# MANEA_TCAD_PROIECT_Sheet1.net
KiCad netlist of a schematic drawn in Altium Designer
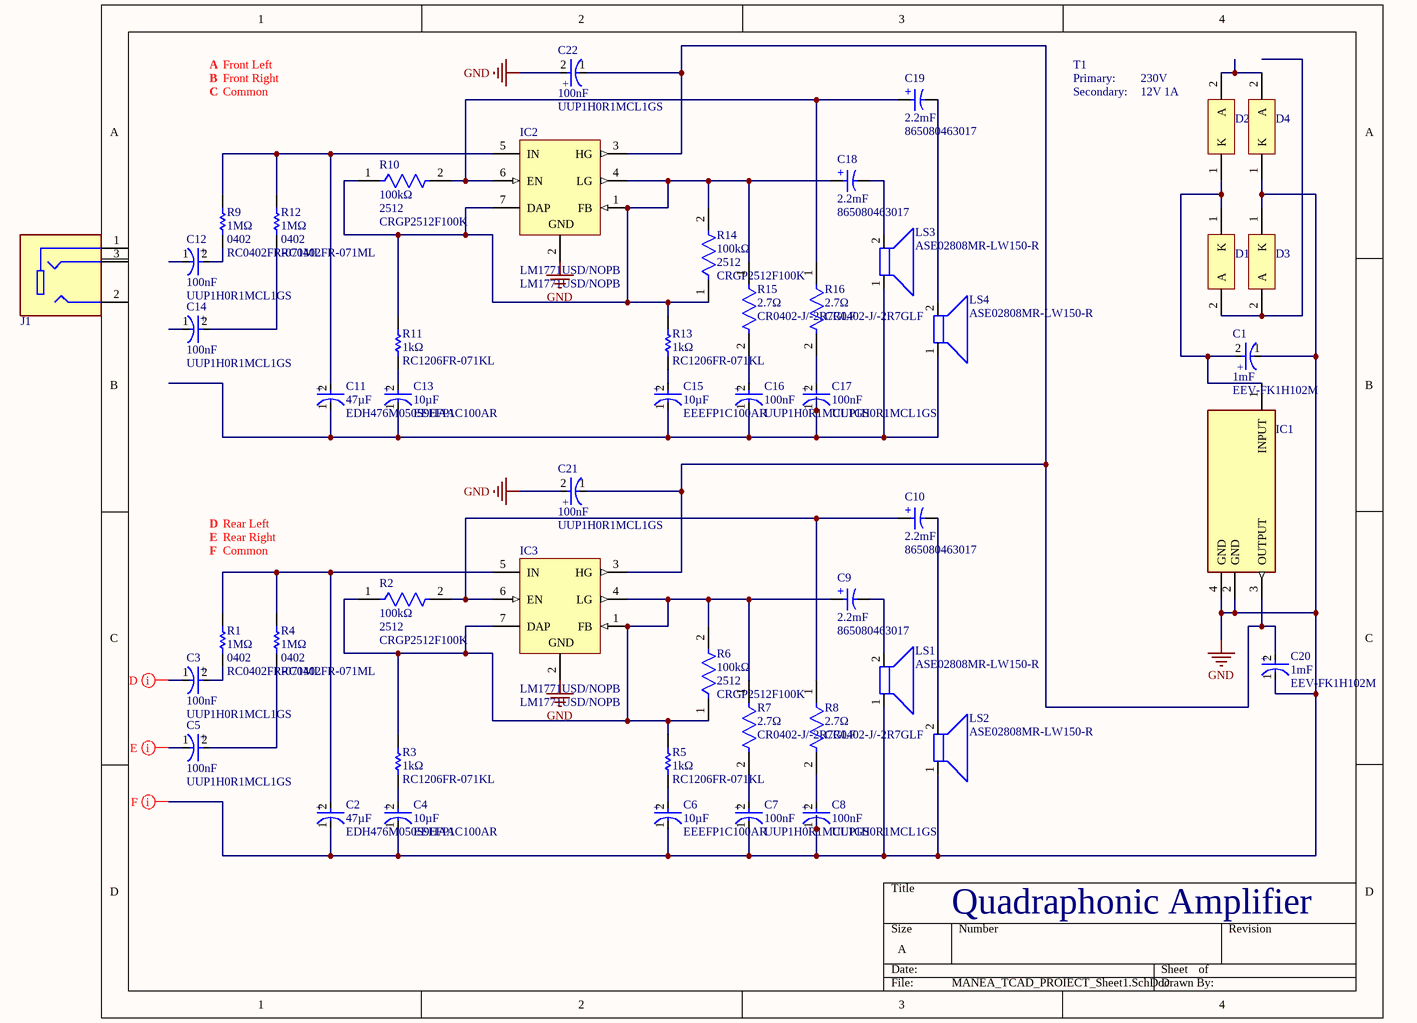
[diagram p0: MANEA_TCAD_PROIECT_Sheet1.SchDoc]

(export (version "E")
  (design (tool "Eeschema 10.0.6"))
  (components
    (comp (ref "C1")
      (value "EEV-FK1H102M")
      (footprint "FP-FK-J16-MFG")
      (description "Radial Can - SMD ALUMINUM ELECTROLYTIC CAPACITOR FK 50V 1000muF 卤20% 0.630Dia 16.00mm")
      (fields
        (field (name "MANUFACTURER") "Panasonic")
        (field (name "TOLERANCE") "20%")
        (field (name "ALTIUM_VALUE") "1mF")
      )
      (libsource (lib "MANEA_TCAD_PROIECT_Schlib") (part "EEV-FK1H102M"))
    )
    (comp (ref "C2")
      (value "EDH476M050S9HAA")
      (footprint "FP-EDH476M050S9HAA-IPC_A")
      (description "Radial Can - SMD ALUMINUM ELECTROLYTIC CAPACITOR EDH 50V 47muF ±20% 0.248Dia 6.30mm")
      (fields
        (field (name "MANUFACTURER") "Yageo Group")
        (field (name "TOLERANCE") "20%")
        (field (name "ALTIUM_VALUE") "47µF")
      )
      (libsource (lib "MANEA_TCAD_PROIECT_Schlib") (part "EDH476M050S9HAA"))
    )
    (comp (ref "C3")
      (value "UUP1H0R1MCL1GS")
      (footprint "FP-UUP1H0R1MCL1GS-MFG")
      (description "Radial Can - SMD ALUMINUM ELECTROLYTIC CAPACITOR UUP 50V 0.1muF ±20% 0.157Dia 4.00mm")
      (fields
        (field (name "MANUFACTURER") "Nichicon")
        (field (name "TOLERANCE") "20%")
        (field (name "ALTIUM_VALUE") "100nF")
      )
      (libsource (lib "MANEA_TCAD_PROIECT_Schlib") (part "UUP1H0R1MCL1GS"))
    )
    (comp (ref "C4")
      (value "EEEFP1C100AR")
      (footprint "FP-FPB-MFG")
      (description "Capacitor Aluminum 10uF 16VDC 20% 4 X 5.8mm SMD 0.85 Ohm 160mA 2000 hr Embossed T/R")
      (fields
        (field (name "MANUFACTURER") "Panasonic")
        (field (name "TOLERANCE") "20%")
        (field (name "ALTIUM_VALUE") "10µF")
      )
      (libsource (lib "MANEA_TCAD_PROIECT_Schlib") (part "EEEFP1C100AR"))
    )
    (comp (ref "C5")
      (value "UUP1H0R1MCL1GS")
      (footprint "FP-UUP1H0R1MCL1GS-MFG")
      (description "Radial Can - SMD ALUMINUM ELECTROLYTIC CAPACITOR UUP 50V 0.1muF ±20% 0.157Dia 4.00mm")
      (fields
        (field (name "MANUFACTURER") "Nichicon")
        (field (name "TOLERANCE") "20%")
        (field (name "ALTIUM_VALUE") "100nF")
      )
      (libsource (lib "MANEA_TCAD_PROIECT_Schlib") (part "UUP1H0R1MCL1GS"))
    )
    (comp (ref "C6")
      (value "EEEFP1C100AR")
      (footprint "FP-FPB-MFG")
      (description "Capacitor Aluminum 10uF 16VDC 20% 4 X 5.8mm SMD 0.85 Ohm 160mA 2000 hr Embossed T/R")
      (fields
        (field (name "MANUFACTURER") "Panasonic")
        (field (name "TOLERANCE") "20%")
        (field (name "ALTIUM_VALUE") "10µF")
      )
      (libsource (lib "MANEA_TCAD_PROIECT_Schlib") (part "EEEFP1C100AR"))
    )
    (comp (ref "C7")
      (value "UUP1H0R1MCL1GS")
      (footprint "FP-UUP1H0R1MCL1GS-MFG")
      (description "Radial Can - SMD ALUMINUM ELECTROLYTIC CAPACITOR UUP 50V 0.1muF ±20% 0.157Dia 4.00mm")
      (fields
        (field (name "MANUFACTURER") "Nichicon")
        (field (name "TOLERANCE") "20%")
        (field (name "ALTIUM_VALUE") "100nF")
      )
      (libsource (lib "MANEA_TCAD_PROIECT_Schlib") (part "UUP1H0R1MCL1GS"))
    )
    (comp (ref "C8")
      (value "UUP1H0R1MCL1GS")
      (footprint "FP-UUP1H0R1MCL1GS-MFG")
      (description "Radial Can - SMD ALUMINUM ELECTROLYTIC CAPACITOR UUP 50V 0.1muF ±20% 0.157Dia 4.00mm")
      (fields
        (field (name "MANUFACTURER") "Nichicon")
        (field (name "TOLERANCE") "20%")
        (field (name "ALTIUM_VALUE") "100nF")
      )
      (libsource (lib "MANEA_TCAD_PROIECT_Schlib") (part "UUP1H0R1MCL1GS"))
    )
    (comp (ref "C9")
      (value "865080463017")
      (footprint "WCAP-ASLI_D16H17")
      (description "SMD Aluminium Electrolytic Capacitor, WCAP-ASLI Series, 2200 F, 25 V, Radial Can - SMD, 16 mm")
      (fields
        (field (name "MANUFACTURER") "Wurth Elektronik")
        (field (name "TOLERANCE") "20%")
        (field (name "ALTIUM_VALUE") "2.2mF")
      )
      (libsource (lib "MANEA_TCAD_PROIECT_Schlib") (part "865080463017"))
    )
    (comp (ref "C10")
      (value "865080463017")
      (footprint "WCAP-ASLI_D16H17")
      (description "SMD Aluminium Electrolytic Capacitor, WCAP-ASLI Series, 2200 F, 25 V, Radial Can - SMD, 16 mm")
      (fields
        (field (name "MANUFACTURER") "Wurth Elektronik")
        (field (name "TOLERANCE") "20%")
        (field (name "ALTIUM_VALUE") "2.2mF")
      )
      (libsource (lib "MANEA_TCAD_PROIECT_Schlib") (part "865080463017"))
    )
    (comp (ref "C11")
      (value "EDH476M050S9HAA")
      (footprint "FP-EDH476M050S9HAA-IPC_A")
      (description "Radial Can - SMD ALUMINUM ELECTROLYTIC CAPACITOR EDH 50V 47muF ±20% 0.248Dia 6.30mm")
      (fields
        (field (name "MANUFACTURER") "Yageo Group")
        (field (name "TOLERANCE") "20%")
        (field (name "ALTIUM_VALUE") "47µF")
      )
      (libsource (lib "MANEA_TCAD_PROIECT_Schlib") (part "EDH476M050S9HAA"))
    )
    (comp (ref "C12")
      (value "UUP1H0R1MCL1GS")
      (footprint "FP-UUP1H0R1MCL1GS-MFG")
      (description "Radial Can - SMD ALUMINUM ELECTROLYTIC CAPACITOR UUP 50V 0.1muF ±20% 0.157Dia 4.00mm")
      (fields
        (field (name "MANUFACTURER") "Nichicon")
        (field (name "TOLERANCE") "20%")
        (field (name "ALTIUM_VALUE") "100nF")
      )
      (libsource (lib "MANEA_TCAD_PROIECT_Schlib") (part "UUP1H0R1MCL1GS"))
    )
    (comp (ref "C13")
      (value "EEEFP1C100AR")
      (footprint "FP-FPB-MFG")
      (description "Capacitor Aluminum 10uF 16VDC 20% 4 X 5.8mm SMD 0.85 Ohm 160mA 2000 hr Embossed T/R")
      (fields
        (field (name "MANUFACTURER") "Panasonic")
        (field (name "TOLERANCE") "20%")
        (field (name "ALTIUM_VALUE") "10µF")
      )
      (libsource (lib "MANEA_TCAD_PROIECT_Schlib") (part "EEEFP1C100AR"))
    )
    (comp (ref "C14")
      (value "UUP1H0R1MCL1GS")
      (footprint "FP-UUP1H0R1MCL1GS-MFG")
      (description "Radial Can - SMD ALUMINUM ELECTROLYTIC CAPACITOR UUP 50V 0.1muF ±20% 0.157Dia 4.00mm")
      (fields
        (field (name "MANUFACTURER") "Nichicon")
        (field (name "TOLERANCE") "20%")
        (field (name "ALTIUM_VALUE") "100nF")
      )
      (libsource (lib "MANEA_TCAD_PROIECT_Schlib") (part "UUP1H0R1MCL1GS"))
    )
    (comp (ref "C15")
      (value "EEEFP1C100AR")
      (footprint "FP-FPB-MFG")
      (description "Capacitor Aluminum 10uF 16VDC 20% 4 X 5.8mm SMD 0.85 Ohm 160mA 2000 hr Embossed T/R")
      (fields
        (field (name "MANUFACTURER") "Panasonic")
        (field (name "TOLERANCE") "20%")
        (field (name "ALTIUM_VALUE") "10µF")
      )
      (libsource (lib "MANEA_TCAD_PROIECT_Schlib") (part "EEEFP1C100AR"))
    )
    (comp (ref "C16")
      (value "UUP1H0R1MCL1GS")
      (footprint "FP-UUP1H0R1MCL1GS-MFG")
      (description "Radial Can - SMD ALUMINUM ELECTROLYTIC CAPACITOR UUP 50V 0.1muF ±20% 0.157Dia 4.00mm")
      (fields
        (field (name "MANUFACTURER") "Nichicon")
        (field (name "TOLERANCE") "20%")
        (field (name "ALTIUM_VALUE") "100nF")
      )
      (libsource (lib "MANEA_TCAD_PROIECT_Schlib") (part "UUP1H0R1MCL1GS"))
    )
    (comp (ref "C17")
      (value "UUP1H0R1MCL1GS")
      (footprint "FP-UUP1H0R1MCL1GS-MFG")
      (description "Radial Can - SMD ALUMINUM ELECTROLYTIC CAPACITOR UUP 50V 0.1muF ±20% 0.157Dia 4.00mm")
      (fields
        (field (name "MANUFACTURER") "Nichicon")
        (field (name "TOLERANCE") "20%")
        (field (name "ALTIUM_VALUE") "100nF")
      )
      (libsource (lib "MANEA_TCAD_PROIECT_Schlib") (part "UUP1H0R1MCL1GS"))
    )
    (comp (ref "C18")
      (value "865080463017")
      (footprint "WCAP-ASLI_D16H17")
      (description "SMD Aluminium Electrolytic Capacitor, WCAP-ASLI Series, 2200 F, 25 V, Radial Can - SMD, 16 mm")
      (fields
        (field (name "MANUFACTURER") "Wurth Elektronik")
        (field (name "TOLERANCE") "20%")
        (field (name "ALTIUM_VALUE") "2.2mF")
      )
      (libsource (lib "MANEA_TCAD_PROIECT_Schlib") (part "865080463017"))
    )
    (comp (ref "C19")
      (value "865080463017")
      (footprint "WCAP-ASLI_D16H17")
      (description "SMD Aluminium Electrolytic Capacitor, WCAP-ASLI Series, 2200 F, 25 V, Radial Can - SMD, 16 mm")
      (fields
        (field (name "MANUFACTURER") "Wurth Elektronik")
        (field (name "TOLERANCE") "20%")
        (field (name "ALTIUM_VALUE") "2.2mF")
      )
      (libsource (lib "MANEA_TCAD_PROIECT_Schlib") (part "865080463017"))
    )
    (comp (ref "C20")
      (value "EEV-FK1H102M")
      (footprint "FP-FK-J16-MFG")
      (description "Radial Can - SMD ALUMINUM ELECTROLYTIC CAPACITOR FK 50V 1000muF 卤20% 0.630Dia 16.00mm")
      (fields
        (field (name "MANUFACTURER") "Panasonic")
        (field (name "TOLERANCE") "20%")
        (field (name "ALTIUM_VALUE") "1mF")
      )
      (libsource (lib "MANEA_TCAD_PROIECT_Schlib") (part "EEV-FK1H102M"))
    )
    (comp (ref "C21")
      (value "UUP1H0R1MCL1GS")
      (footprint "FP-UUP1H0R1MCL1GS-MFG")
      (description "Radial Can - SMD ALUMINUM ELECTROLYTIC CAPACITOR UUP 50V 0.1muF ±20% 0.157Dia 4.00mm")
      (fields
        (field (name "MANUFACTURER") "Nichicon")
        (field (name "TOLERANCE") "20%")
        (field (name "ALTIUM_VALUE") "100nF")
      )
      (libsource (lib "MANEA_TCAD_PROIECT_Schlib") (part "UUP1H0R1MCL1GS"))
    )
    (comp (ref "C22")
      (value "UUP1H0R1MCL1GS")
      (footprint "FP-UUP1H0R1MCL1GS-MFG")
      (description "Radial Can - SMD ALUMINUM ELECTROLYTIC CAPACITOR UUP 50V 0.1muF ±20% 0.157Dia 4.00mm")
      (fields
        (field (name "MANUFACTURER") "Nichicon")
        (field (name "TOLERANCE") "20%")
        (field (name "ALTIUM_VALUE") "100nF")
      )
      (libsource (lib "MANEA_TCAD_PROIECT_Schlib") (part "UUP1H0R1MCL1GS"))
    )
    (comp (ref "D1")
      (value "1N4001")
      (footprint "ONSC-AXIAL_LEAD-2-59-10_P")
      (description "Rectifier Diode Switching 50V 1A 2-Pin DO-41 Box / DIODE GEN PURP 50V 1A DO41")
      (libsource (lib "MANEA_TCAD_PROIECT_Schlib") (part "D1N4001"))
    )
    (comp (ref "D2")
      (value "1N4001")
      (footprint "ONSC-AXIAL_LEAD-2-59-10_P")
      (description "Rectifier Diode Switching 50V 1A 2-Pin DO-41 Box / DIODE GEN PURP 50V 1A DO41")
      (libsource (lib "") (part "D1N4001_1"))
    )
    (comp (ref "D3")
      (value "1N4001")
      (footprint "ONSC-AXIAL_LEAD-2-59-10_P")
      (description "Rectifier Diode Switching 50V 1A 2-Pin DO-41 Box / DIODE GEN PURP 50V 1A DO41")
      (libsource (lib "MANEA_TCAD_PROIECT_Schlib") (part "D1N4001"))
    )
    (comp (ref "D4")
      (value "1N4001")
      (footprint "ONSC-AXIAL_LEAD-2-59-10_P")
      (description "Rectifier Diode Switching 50V 1A 2-Pin DO-41 Box / DIODE GEN PURP 50V 1A DO41")
      (libsource (lib "") (part "D1N4001_1"))
    )
    (comp (ref "IC1")
      (value "LM7812SX/NOPB")
      (footprint "FP-KTT0003B-MFG")
      (description "1.5-A, 30-V, linear voltage regulator 3-DDPAK/TO-263 0 to 125")
      (fields (field (name "MANUFACTURER") "Texas Instruments"))
      (libsource (lib "MANEA_TCAD_PROIECT_Schlib") (part "LM7812SX/NOPB"))
    )
    (comp (ref "IC2")
      (value "LM1771USD/NOPB")
      (footprint "NGG0006A_V")
      (description "LM1771 Buck Tape & Reel (TR) e3 DC to DC switching controller 400muA 6A 800mum 4.5V")
      (fields
        (field (name "MANUFACTURER") "Texas Instruments")
        (field (name "MANUFACTURER PART NUMBER") "LM1771USD/NOPB")
      )
      (libsource (lib "MANEA_TCAD_PROIECT_Schlib") (part "LM1771USD/NOPB"))
    )
    (comp (ref "IC3")
      (value "LM1771USD/NOPB")
      (footprint "NGG0006A_V")
      (description "LM1771 Buck Tape & Reel (TR) e3 DC to DC switching controller 400muA 6A 800mum 4.5V")
      (fields
        (field (name "MANUFACTURER") "Texas Instruments")
        (field (name "MANUFACTURER PART NUMBER") "LM1771USD/NOPB")
      )
      (libsource (lib "MANEA_TCAD_PROIECT_Schlib") (part "LM1771USD/NOPB"))
    )
    (comp (ref "J1")
      (value "SJ1-3523N")
      (footprint "CUI_SJ1-3523N")
      (description "3.5 mm, Stereo, Right Angle, Through Hole, Audio Jack Connector")
      (fields (field (name "MANUFACTURER") "Same Sky"))
      (libsource (lib "MANEA_TCAD_PROIECT_Schlib") (part "SJ1-3523N"))
    )
    (comp (ref "LS1")
      (value "ASE02808MR-LW150-R")
      (footprint "FP-ASE02808MR-LW150-R-MFG")
      (description "Speakers & Transducers 28mm SPEAKER w/ENCL 2 W 8 OHM 82 DB")
      (fields (field (name "MANUFACTURER") "PUI Audio"))
      (libsource (lib "MANEA_TCAD_PROIECT_Schlib") (part "ASE02808MR-LW150-R"))
    )
    (comp (ref "LS2")
      (value "ASE02808MR-LW150-R")
      (footprint "FP-ASE02808MR-LW150-R-MFG")
      (description "Speakers & Transducers 28mm SPEAKER w/ENCL 2 W 8 OHM 82 DB")
      (fields (field (name "MANUFACTURER") "PUI Audio"))
      (libsource (lib "MANEA_TCAD_PROIECT_Schlib") (part "ASE02808MR-LW150-R"))
    )
    (comp (ref "LS3")
      (value "ASE02808MR-LW150-R")
      (footprint "FP-ASE02808MR-LW150-R-MFG")
      (description "Speakers & Transducers 28mm SPEAKER w/ENCL 2 W 8 OHM 82 DB")
      (fields (field (name "MANUFACTURER") "PUI Audio"))
      (libsource (lib "MANEA_TCAD_PROIECT_Schlib") (part "ASE02808MR-LW150-R"))
    )
    (comp (ref "LS4")
      (value "ASE02808MR-LW150-R")
      (footprint "FP-ASE02808MR-LW150-R-MFG")
      (description "Speakers & Transducers 28mm SPEAKER w/ENCL 2 W 8 OHM 82 DB")
      (fields (field (name "MANUFACTURER") "PUI Audio"))
      (libsource (lib "MANEA_TCAD_PROIECT_Schlib") (part "ASE02808MR-LW150-R"))
    )
    (comp (ref "R1")
      (value "RC0402FR-071ML")
      (footprint "RESC1005X40X25NL05T10")
      (description "Res Thick Film 0402 1M Ohm 1% 0.063W(1/16W) ±100ppm/C Pad SMD T/R")
      (fields
        (field (name "MANUFACTURER") "Yageo Group")
        (field (name "TOLERANCE") "1%")
        (field (name "CASE/PACKAGE") "0402")
        (field (name "ALTIUM_VALUE") "1MΩ")
      )
      (libsource (lib "MANEA_TCAD_PROIECT_Schlib") (part "RC0402FR-071ML"))
    )
    (comp (ref "R2")
      (value "CRGP2512F100K")
      (footprint "FP-CRGP2512-IPC_A")
      (description "Res Thick Film 2512 100K Ohm 1% 2W ±100ppm/°C Pad SMD T/R Automotive AEC-Q200")
      (fields
        (field (name "MANUFACTURER") "TE Connectivity")
        (field (name "TOLERANCE") "1%")
        (field (name "CASE/PACKAGE") "2512")
        (field (name "ALTIUM_VALUE") "100kΩ")
      )
      (libsource (lib "MANEA_TCAD_PROIECT_Schlib") (part "CRGP2512F100K"))
    )
    (comp (ref "R3")
      (value "RC1206FR-071KL")
      (footprint "RESC3116X65X40NL10T20")
      (description "250mW Thick Film Resistors 200V ±100ppm/℃ ±1% 1kΩ 1206 Chip Resistor - Surface Mount ROHS")
      (fields
        (field (name "MANUFACTURER") "Yageo Group")
        (field (name "TOLERANCE") "1%")
        (field (name "ALTIUM_VALUE") "1kΩ")
      )
      (libsource (lib "MANEA_TCAD_PROIECT_Schlib") (part "RC1206FR-071KL"))
    )
    (comp (ref "R4")
      (value "RC0402FR-071ML")
      (footprint "RESC1005X40X25NL05T10")
      (description "Res Thick Film 0402 1M Ohm 1% 0.063W(1/16W) ±100ppm/C Pad SMD T/R")
      (fields
        (field (name "MANUFACTURER") "Yageo Group")
        (field (name "TOLERANCE") "1%")
        (field (name "CASE/PACKAGE") "0402")
        (field (name "ALTIUM_VALUE") "1MΩ")
      )
      (libsource (lib "MANEA_TCAD_PROIECT_Schlib") (part "RC0402FR-071ML"))
    )
    (comp (ref "R5")
      (value "RC1206FR-071KL")
      (footprint "RESC3116X65X40NL10T20")
      (description "250mW Thick Film Resistors 200V ±100ppm/℃ ±1% 1kΩ 1206 Chip Resistor - Surface Mount ROHS")
      (fields
        (field (name "MANUFACTURER") "Yageo Group")
        (field (name "TOLERANCE") "1%")
        (field (name "ALTIUM_VALUE") "1kΩ")
      )
      (libsource (lib "MANEA_TCAD_PROIECT_Schlib") (part "RC1206FR-071KL"))
    )
    (comp (ref "R6")
      (value "CRGP2512F100K")
      (footprint "FP-CRGP2512-IPC_A")
      (description "Res Thick Film 2512 100K Ohm 1% 2W ±100ppm/°C Pad SMD T/R Automotive AEC-Q200")
      (fields
        (field (name "MANUFACTURER") "TE Connectivity")
        (field (name "TOLERANCE") "1%")
        (field (name "CASE/PACKAGE") "2512")
        (field (name "ALTIUM_VALUE") "100kΩ")
      )
      (libsource (lib "MANEA_TCAD_PROIECT_Schlib") (part "CRGP2512F100K"))
    )
    (comp (ref "R7")
      (value "CR0402-J/-2R7GLF")
      (footprint "FP-CR0402-MFG")
      (description "CR0402 FIXED RESISTOR 0402 (1005Metric) Chip Resistor ±5% -250/ +500ppm/C 2.7Ohm 0.063W 1/16W")
      (fields
        (field (name "MANUFACTURER") "Bourns")
        (field (name "TOLERANCE") "5%")
        (field (name "ALTIUM_VALUE") "2.7Ω")
      )
      (libsource (lib "MANEA_TCAD_PROIECT_Schlib") (part "CR0402-J/-2R7GLF"))
    )
    (comp (ref "R8")
      (value "CR0402-J/-2R7GLF")
      (footprint "FP-CR0402-MFG")
      (description "CR0402 FIXED RESISTOR 0402 (1005Metric) Chip Resistor ±5% -250/ +500ppm/C 2.7Ohm 0.063W 1/16W")
      (fields
        (field (name "MANUFACTURER") "Bourns")
        (field (name "TOLERANCE") "5%")
        (field (name "ALTIUM_VALUE") "2.7Ω")
      )
      (libsource (lib "MANEA_TCAD_PROIECT_Schlib") (part "CR0402-J/-2R7GLF"))
    )
    (comp (ref "R9")
      (value "RC0402FR-071ML")
      (footprint "RESC1005X40X25NL05T10")
      (description "Res Thick Film 0402 1M Ohm 1% 0.063W(1/16W) ±100ppm/C Pad SMD T/R")
      (fields
        (field (name "MANUFACTURER") "Yageo Group")
        (field (name "TOLERANCE") "1%")
        (field (name "CASE/PACKAGE") "0402")
        (field (name "ALTIUM_VALUE") "1MΩ")
      )
      (libsource (lib "MANEA_TCAD_PROIECT_Schlib") (part "RC0402FR-071ML"))
    )
    (comp (ref "R10")
      (value "CRGP2512F100K")
      (footprint "FP-CRGP2512-IPC_A")
      (description "Res Thick Film 2512 100K Ohm 1% 2W ±100ppm/°C Pad SMD T/R Automotive AEC-Q200")
      (fields
        (field (name "MANUFACTURER") "TE Connectivity")
        (field (name "TOLERANCE") "1%")
        (field (name "CASE/PACKAGE") "2512")
        (field (name "ALTIUM_VALUE") "100kΩ")
      )
      (libsource (lib "MANEA_TCAD_PROIECT_Schlib") (part "CRGP2512F100K"))
    )
    (comp (ref "R11")
      (value "RC1206FR-071KL")
      (footprint "RESC3116X65X40NL10T20")
      (description "250mW Thick Film Resistors 200V ±100ppm/℃ ±1% 1kΩ 1206 Chip Resistor - Surface Mount ROHS")
      (fields
        (field (name "MANUFACTURER") "Yageo Group")
        (field (name "TOLERANCE") "1%")
        (field (name "ALTIUM_VALUE") "1kΩ")
      )
      (libsource (lib "MANEA_TCAD_PROIECT_Schlib") (part "RC1206FR-071KL"))
    )
    (comp (ref "R12")
      (value "RC0402FR-071ML")
      (footprint "RESC1005X40X25NL05T10")
      (description "Res Thick Film 0402 1M Ohm 1% 0.063W(1/16W) ±100ppm/C Pad SMD T/R")
      (fields
        (field (name "MANUFACTURER") "Yageo Group")
        (field (name "TOLERANCE") "1%")
        (field (name "CASE/PACKAGE") "0402")
        (field (name "ALTIUM_VALUE") "1MΩ")
      )
      (libsource (lib "MANEA_TCAD_PROIECT_Schlib") (part "RC0402FR-071ML"))
    )
    (comp (ref "R13")
      (value "RC1206FR-071KL")
      (footprint "RESC3116X65X40NL10T20")
      (description "250mW Thick Film Resistors 200V ±100ppm/℃ ±1% 1kΩ 1206 Chip Resistor - Surface Mount ROHS")
      (fields
        (field (name "MANUFACTURER") "Yageo Group")
        (field (name "TOLERANCE") "1%")
        (field (name "ALTIUM_VALUE") "1kΩ")
      )
      (libsource (lib "MANEA_TCAD_PROIECT_Schlib") (part "RC1206FR-071KL"))
    )
    (comp (ref "R14")
      (value "CRGP2512F100K")
      (footprint "FP-CRGP2512-IPC_A")
      (description "Res Thick Film 2512 100K Ohm 1% 2W ±100ppm/°C Pad SMD T/R Automotive AEC-Q200")
      (fields
        (field (name "MANUFACTURER") "TE Connectivity")
        (field (name "TOLERANCE") "1%")
        (field (name "CASE/PACKAGE") "2512")
        (field (name "ALTIUM_VALUE") "100kΩ")
      )
      (libsource (lib "MANEA_TCAD_PROIECT_Schlib") (part "CRGP2512F100K"))
    )
    (comp (ref "R15")
      (value "CR0402-J/-2R7GLF")
      (footprint "FP-CR0402-MFG")
      (description "CR0402 FIXED RESISTOR 0402 (1005Metric) Chip Resistor ±5% -250/ +500ppm/C 2.7Ohm 0.063W 1/16W")
      (fields
        (field (name "MANUFACTURER") "Bourns")
        (field (name "TOLERANCE") "5%")
        (field (name "ALTIUM_VALUE") "2.7Ω")
      )
      (libsource (lib "MANEA_TCAD_PROIECT_Schlib") (part "CR0402-J/-2R7GLF"))
    )
    (comp (ref "R16")
      (value "CR0402-J/-2R7GLF")
      (footprint "FP-CR0402-MFG")
      (description "CR0402 FIXED RESISTOR 0402 (1005Metric) Chip Resistor ±5% -250/ +500ppm/C 2.7Ohm 0.063W 1/16W")
      (fields
        (field (name "MANUFACTURER") "Bourns")
        (field (name "TOLERANCE") "5%")
        (field (name "ALTIUM_VALUE") "2.7Ω")
      )
      (libsource (lib "MANEA_TCAD_PROIECT_Schlib") (part "CR0402-J/-2R7GLF"))
    )
  )
  (nets
    (net (code "1") (name "GND") (class "Default")
      (node (ref "C1") (pin "1") (pinfunction "C_1") (pintype "passive"))
      (node (ref "C2") (pin "1") (pinfunction "C_1") (pintype "passive"))
      (node (ref "C20") (pin "1") (pinfunction "C_1") (pintype "passive"))
      (node (ref "C21") (pin "2") (pinfunction "A_2") (pintype "passive"))
      (node (ref "C22") (pin "2") (pinfunction "A_2") (pintype "passive"))
      (node (ref "C4") (pin "1") (pinfunction "C_1") (pintype "passive"))
      (node (ref "C6") (pin "1") (pinfunction "C_1") (pintype "passive"))
      (node (ref "C7") (pin "1") (pinfunction "C_1") (pintype "passive"))
      (node (ref "C8") (pin "1") (pinfunction "C_1") (pintype "passive"))
      (node (ref "D3") (pin "1") (pinfunction "K_1") (pintype "passive"))
      (node (ref "D4") (pin "1") (pinfunction "K_1") (pintype "passive"))
      (node (ref "IC1") (pin "2") (pinfunction "GND_2") (pintype "power_in"))
      (node (ref "IC1") (pin "4") (pinfunction "GND_4") (pintype "power_in"))
      (node (ref "IC2") (pin "2") (pinfunction "GND_2") (pintype "power_in"))
      (node (ref "IC3") (pin "2") (pinfunction "GND_2") (pintype "power_in"))
      (node (ref "LS1") (pin "1") (pinfunction "1_1") (pintype "passive"))
      (node (ref "LS2") (pin "1") (pinfunction "1_1") (pintype "passive"))
    )
    (net (code "2") (name "Net-(C1-A)") (class "Default")
      (node (ref "C1") (pin "2") (pinfunction "A_2") (pintype "passive"))
      (node (ref "D1") (pin "1") (pinfunction "K_1") (pintype "passive"))
      (node (ref "D2") (pin "1") (pinfunction "K_1") (pintype "passive"))
      (node (ref "IC1") (pin "1") (pinfunction "INPUT_1") (pintype "power_in"))
    )
    (net (code "3") (name "Net-(C2-A)") (class "Default")
      (node (ref "C2") (pin "2") (pinfunction "A_2") (pintype "passive"))
      (node (ref "IC3") (pin "5") (pinfunction "IN_5") (pintype "power_in"))
      (node (ref "R1") (pin "2") (pinfunction "2_2") (pintype "passive"))
      (node (ref "R4") (pin "2") (pinfunction "2_2") (pintype "passive"))
    )
    (net (code "4") (name "Net-(C3-A)") (class "Default")
      (node (ref "C3") (pin "2") (pinfunction "A_2") (pintype "passive"))
      (node (ref "R1") (pin "1") (pinfunction "1_1") (pintype "passive"))
    )
    (net (code "5") (name "Net-(C4-A)") (class "Default")
      (node (ref "C4") (pin "2") (pinfunction "A_2") (pintype "passive"))
      (node (ref "R3") (pin "1") (pinfunction "1_1") (pintype "passive"))
    )
    (net (code "6") (name "Net-(C5-A)") (class "Default")
      (node (ref "C5") (pin "2") (pinfunction "A_2") (pintype "passive"))
      (node (ref "R4") (pin "1") (pinfunction "1_1") (pintype "passive"))
    )
    (net (code "7") (name "Net-(C6-A)") (class "Default")
      (node (ref "C6") (pin "2") (pinfunction "A_2") (pintype "passive"))
      (node (ref "R5") (pin "1") (pinfunction "1_1") (pintype "passive"))
    )
    (net (code "8") (name "Net-(C7-A)") (class "Default")
      (node (ref "C7") (pin "2") (pinfunction "A_2") (pintype "passive"))
      (node (ref "R7") (pin "2") (pinfunction "2_2") (pintype "passive"))
    )
    (net (code "9") (name "Net-(C8-A)") (class "Default")
      (node (ref "C8") (pin "2") (pinfunction "A_2") (pintype "passive"))
      (node (ref "R8") (pin "2") (pinfunction "2_2") (pintype "passive"))
    )
    (net (code "10") (name "Net-(C9-N)") (class "Default")
      (node (ref "C9") (pin "2") (pinfunction "N_2") (pintype "passive"))
      (node (ref "LS1") (pin "2") (pintype "passive"))
    )
    (net (code "11") (name "Net-(C9-P)") (class "Default")
      (node (ref "C9") (pin "1") (pinfunction "P_1") (pintype "passive"))
      (node (ref "IC3") (pin "1") (pinfunction "FB_1") (pintype "input"))
      (node (ref "IC3") (pin "4") (pinfunction "LG_4") (pintype "output"))
      (node (ref "IC3") (pin "7") (pinfunction "DAP_7") (pintype "power_in"))
      (node (ref "R2") (pin "1") (pinfunction "1_1") (pintype "passive"))
      (node (ref "R3") (pin "2") (pinfunction "2_2") (pintype "passive"))
      (node (ref "R5") (pin "2") (pinfunction "2_2") (pintype "passive"))
      (node (ref "R6") (pin "1") (pinfunction "1_1") (pintype "passive"))
      (node (ref "R6") (pin "2") (pinfunction "2_2") (pintype "passive"))
      (node (ref "R7") (pin "1") (pinfunction "1_1") (pintype "passive"))
    )
    (net (code "12") (name "Net-(C10-N)") (class "Default")
      (node (ref "C10") (pin "2") (pinfunction "N_2") (pintype "passive"))
      (node (ref "LS2") (pin "2") (pintype "passive"))
    )
    (net (code "13") (name "Net-(C10-P)") (class "Default")
      (node (ref "C10") (pin "1") (pinfunction "P_1") (pintype "passive"))
      (node (ref "IC3") (pin "6") (pinfunction "EN_6") (pintype "input"))
      (node (ref "R2") (pin "2") (pinfunction "2_2") (pintype "passive"))
      (node (ref "R8") (pin "1") (pinfunction "1_1") (pintype "passive"))
    )
    (net (code "14") (name "Net-(C11-A)") (class "Default")
      (node (ref "C11") (pin "2") (pinfunction "A_2") (pintype "passive"))
      (node (ref "IC2") (pin "5") (pinfunction "IN_5") (pintype "power_in"))
      (node (ref "R12") (pin "2") (pinfunction "2_2") (pintype "passive"))
      (node (ref "R9") (pin "2") (pinfunction "2_2") (pintype "passive"))
    )
    (net (code "15") (name "Net-(C11-C)") (class "Default")
      (node (ref "C11") (pin "1") (pinfunction "C_1") (pintype "passive"))
      (node (ref "C13") (pin "1") (pinfunction "C_1") (pintype "passive"))
      (node (ref "C15") (pin "1") (pinfunction "C_1") (pintype "passive"))
      (node (ref "C16") (pin "1") (pinfunction "C_1") (pintype "passive"))
      (node (ref "C17") (pin "1") (pinfunction "C_1") (pintype "passive"))
      (node (ref "LS3") (pin "1") (pinfunction "1_1") (pintype "passive"))
      (node (ref "LS4") (pin "1") (pinfunction "1_1") (pintype "passive"))
    )
    (net (code "16") (name "Net-(C12-A)") (class "Default")
      (node (ref "C12") (pin "2") (pinfunction "A_2") (pintype "passive"))
      (node (ref "R9") (pin "1") (pinfunction "1_1") (pintype "passive"))
    )
    (net (code "17") (name "Net-(C13-A)") (class "Default")
      (node (ref "C13") (pin "2") (pinfunction "A_2") (pintype "passive"))
      (node (ref "R11") (pin "1") (pinfunction "1_1") (pintype "passive"))
    )
    (net (code "18") (name "Net-(C14-A)") (class "Default")
      (node (ref "C14") (pin "2") (pinfunction "A_2") (pintype "passive"))
      (node (ref "R12") (pin "1") (pinfunction "1_1") (pintype "passive"))
    )
    (net (code "19") (name "Net-(C15-A)") (class "Default")
      (node (ref "C15") (pin "2") (pinfunction "A_2") (pintype "passive"))
      (node (ref "R13") (pin "1") (pinfunction "1_1") (pintype "passive"))
    )
    (net (code "20") (name "Net-(C16-A)") (class "Default")
      (node (ref "C16") (pin "2") (pinfunction "A_2") (pintype "passive"))
      (node (ref "R15") (pin "2") (pinfunction "2_2") (pintype "passive"))
    )
    (net (code "21") (name "Net-(C17-A)") (class "Default")
      (node (ref "C17") (pin "2") (pinfunction "A_2") (pintype "passive"))
      (node (ref "R16") (pin "2") (pinfunction "2_2") (pintype "passive"))
    )
    (net (code "22") (name "Net-(C18-N)") (class "Default")
      (node (ref "C18") (pin "2") (pinfunction "N_2") (pintype "passive"))
      (node (ref "LS3") (pin "2") (pintype "passive"))
    )
    (net (code "23") (name "Net-(C18-P)") (class "Default")
      (node (ref "C18") (pin "1") (pinfunction "P_1") (pintype "passive"))
      (node (ref "IC2") (pin "1") (pinfunction "FB_1") (pintype "input"))
      (node (ref "IC2") (pin "4") (pinfunction "LG_4") (pintype "output"))
      (node (ref "IC2") (pin "7") (pinfunction "DAP_7") (pintype "power_in"))
      (node (ref "R10") (pin "1") (pinfunction "1_1") (pintype "passive"))
      (node (ref "R11") (pin "2") (pinfunction "2_2") (pintype "passive"))
      (node (ref "R13") (pin "2") (pinfunction "2_2") (pintype "passive"))
      (node (ref "R14") (pin "1") (pinfunction "1_1") (pintype "passive"))
      (node (ref "R14") (pin "2") (pinfunction "2_2") (pintype "passive"))
      (node (ref "R15") (pin "1") (pinfunction "1_1") (pintype "passive"))
    )
    (net (code "24") (name "Net-(C19-N)") (class "Default")
      (node (ref "C19") (pin "2") (pinfunction "N_2") (pintype "passive"))
      (node (ref "LS4") (pin "2") (pintype "passive"))
    )
    (net (code "25") (name "Net-(C19-P)") (class "Default")
      (node (ref "C19") (pin "1") (pinfunction "P_1") (pintype "passive"))
      (node (ref "IC2") (pin "6") (pinfunction "EN_6") (pintype "input"))
      (node (ref "R10") (pin "2") (pinfunction "2_2") (pintype "passive"))
      (node (ref "R16") (pin "1") (pinfunction "1_1") (pintype "passive"))
    )
    (net (code "26") (name "Net-(C20-A)") (class "Default")
      (node (ref "C20") (pin "2") (pinfunction "A_2") (pintype "passive"))
      (node (ref "C21") (pin "1") (pinfunction "C_1") (pintype "passive"))
      (node (ref "C22") (pin "1") (pinfunction "C_1") (pintype "passive"))
      (node (ref "IC1") (pin "3") (pinfunction "OUTPUT_3") (pintype "output"))
      (node (ref "IC2") (pin "3") (pinfunction "HG_3") (pintype "output"))
      (node (ref "IC3") (pin "3") (pinfunction "HG_3") (pintype "output"))
    )
    (net (code "27") (name "Net-(D1-A)") (class "Default")
      (node (ref "D1") (pin "2") (pinfunction "A_2") (pintype "passive"))
      (node (ref "D3") (pin "2") (pinfunction "A_2") (pintype "passive"))
    )
    (net (code "28") (name "Net-(D2-A)") (class "Default")
      (node (ref "D2") (pin "2") (pinfunction "A_2") (pintype "passive"))
      (node (ref "D4") (pin "2") (pinfunction "A_2") (pintype "passive"))
    )
    (net (code "29") (name "unconnected-(C3-C-Pad1)") (class "Default")
      (node (ref "C3") (pin "1") (pinfunction "C_1") (pintype "passive"))
    )
    (net (code "30") (name "unconnected-(C5-C-Pad1)") (class "Default")
      (node (ref "C5") (pin "1") (pinfunction "C_1") (pintype "passive"))
    )
    (net (code "31") (name "unconnected-(C12-C-Pad1)") (class "Default")
      (node (ref "C12") (pin "1") (pinfunction "C_1") (pintype "passive"))
    )
    (net (code "32") (name "unconnected-(C14-C-Pad1)") (class "Default")
      (node (ref "C14") (pin "1") (pinfunction "C_1") (pintype "passive"))
    )
    (net (code "33") (name "unconnected-(J1-Pad1)") (class "Default")
      (node (ref "J1") (pin "1") (pinfunction "1_1") (pintype "passive"))
    )
    (net (code "34") (name "unconnected-(J1-Pad2)") (class "Default")
      (node (ref "J1") (pin "2") (pinfunction "2_2") (pintype "passive"))
    )
    (net (code "35") (name "unconnected-(J1-Pad3)") (class "Default")
      (node (ref "J1") (pin "3") (pinfunction "3_3") (pintype "passive"))
    )
  )
)
